# 02_PowerSupply.net
KiCad netlist of a schematic drawn in Altium Designer
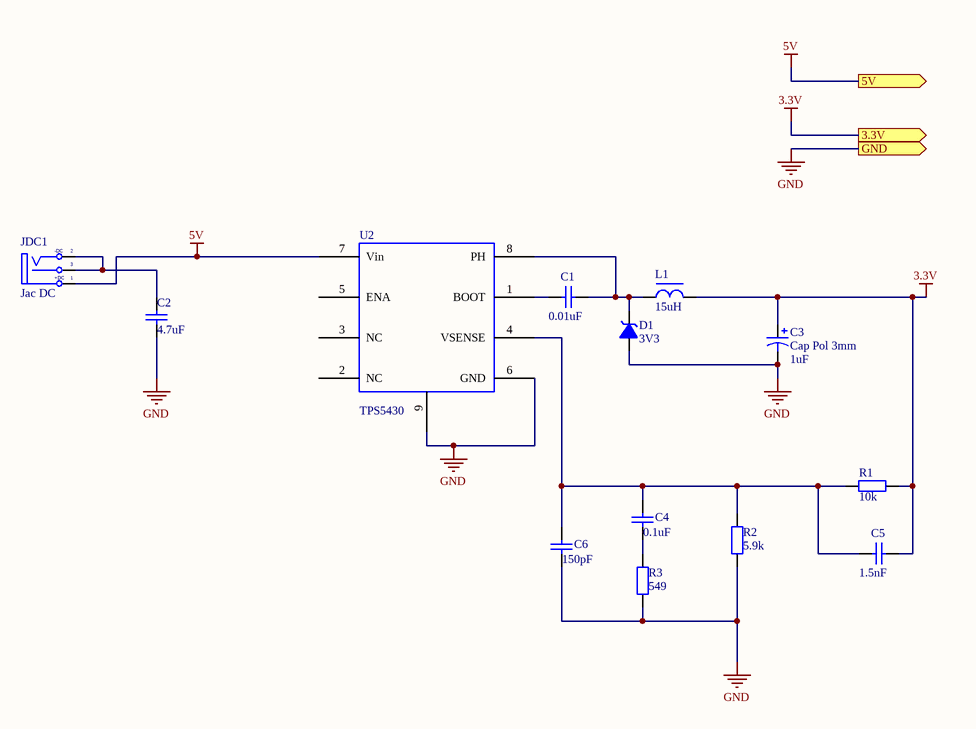
[diagram p0: 02_PowerSupply.SchDoc]

(export (version "E")
  (design (tool "Eeschema 10.0.6"))
  (components
    (comp (ref "C1")
      (value "0.01uF")
      (footprint "C0805")
      (description "Capacitor")
      (fields (field (name "PUBLISHER") "Altium Limited"))
      (libsource (lib "My Library") (part "CapSMD"))
    )
    (comp (ref "C2")
      (value "4.7uF")
      (footprint "C0805")
      (description "Capacitor")
      (fields (field (name "PUBLISHER") "Altium Limited"))
      (libsource (lib "My Library") (part "CapSMD"))
    )
    (comp (ref "C3")
      (value "Cap Pol 3mm")
      (footprint "C3MM")
      (description "Polarized Capacitor (Axial)")
      (fields (field (name "ALTIUM_UNNAMED_1") "1uF") (field (name "PUBLISHER") "Altium Limited"))
      (libsource (lib "My Library") (part "Cap Pol 3mm"))
    )
    (comp (ref "C4")
      (value "0.1uF")
      (footprint "C0805")
      (description "Capacitor")
      (fields (field (name "PUBLISHER") "Altium Limited"))
      (libsource (lib "My Library") (part "CapSMD"))
    )
    (comp (ref "C5")
      (value "1.5nF")
      (footprint "C0805")
      (description "Capacitor")
      (fields (field (name "PUBLISHER") "Altium Limited"))
      (libsource (lib "My Library") (part "CapSMD"))
    )
    (comp (ref "C6")
      (value "150pF")
      (footprint "C0805")
      (description "Capacitor")
      (fields (field (name "PUBLISHER") "Altium Limited"))
      (libsource (lib "My Library") (part "CapSMD"))
    )
    (comp (ref "D1")
      (value "3V3")
      (footprint "DZ0.5A")
      (description "Diode Zenner")
      (libsource (lib "My Library") (part "DZ"))
    )
    (comp (ref "JDC1")
      (value "Jac DC")
      (footprint "DC-IN")
      (description "Jac DC input")
      (libsource (lib "My Library") (part "DCIN"))
    )
    (comp (ref "L1")
      (value "15uH")
      (footprint "L-DIP-M-5.3")
      (description "Inductor")
      (libsource (lib "My Library") (part "L-DIP-1"))
    )
    (comp (ref "R1")
      (value "10k")
      (footprint "DIEN TRO 0805")
      (description "Resistor SMD 0805")
      (fields (field (name "Comment") "R0805") (field (name "PUBLISHER") "Altium Limited"))
      (libsource (lib "") (part "R0805_1"))
    )
    (comp (ref "R2")
      (value "5.9k")
      (footprint "DIEN TRO 0805")
      (description "Resistor SMD 0805")
      (fields (field (name "PUBLISHER") "Altium Limited"))
      (libsource (lib "My Library") (part "R0805"))
    )
    (comp (ref "R3")
      (value "549")
      (footprint "DIEN TRO 0805")
      (description "Resistor SMD 0805")
      (fields (field (name "Comment") "R0805") (field (name "PUBLISHER") "Altium Limited"))
      (libsource (lib "My Library") (part "R0805"))
    )
    (comp (ref "U2")
      (value "TPS5430")
      (footprint "TPS5430-2")
      (fields (field (name "NAME") "TPS5430"))
      (libsource (lib "My Library") (part "TPS5430"))
    )
  )
  (nets
    (net (code "1") (name "3.3V") (class "Default")
      (node (ref "C3") (pin "1") (pinfunction "1_1") (pintype "passive"))
      (node (ref "C5") (pin "1") (pinfunction "1_1") (pintype "passive"))
      (node (ref "L1") (pin "2") (pinfunction "2_2") (pintype "passive"))
      (node (ref "R1") (pin "2") (pinfunction "2_2") (pintype "passive"))
    )
    (net (code "2") (name "5V") (class "Default")
      (node (ref "JDC1") (pin "1") (pinfunction "T_1") (pintype "passive"))
      (node (ref "U2") (pin "7") (pinfunction "Vin_7") (pintype "passive"))
    )
    (net (code "3") (name "GND") (class "Default")
      (node (ref "C2") (pin "1") (pinfunction "1_1") (pintype "passive"))
      (node (ref "C3") (pin "2") (pinfunction "2_2") (pintype "passive"))
      (node (ref "C6") (pin "1") (pinfunction "1_1") (pintype "passive"))
      (node (ref "D1") (pin "1") (pinfunction "A_1") (pintype "passive"))
      (node (ref "R2") (pin "1") (pinfunction "1_1") (pintype "passive"))
      (node (ref "R3") (pin "1") (pinfunction "1_1") (pintype "passive"))
      (node (ref "U2") (pin "6") (pinfunction "GND_6") (pintype "passive"))
      (node (ref "U2") (pin "9") (pinfunction "PWR_PAD_9") (pintype "passive"))
    )
    (net (code "4") (name "Net-(C4-Pad1)") (class "Default")
      (node (ref "C4") (pin "1") (pinfunction "1_1") (pintype "passive"))
      (node (ref "R3") (pin "2") (pinfunction "2_2") (pintype "passive"))
    )
    (net (code "5") (name "Net-(D1-K)") (class "Default")
      (node (ref "C1") (pin "1") (pinfunction "1_1") (pintype "passive"))
      (node (ref "D1") (pin "2") (pinfunction "K_2") (pintype "passive"))
      (node (ref "L1") (pin "1") (pinfunction "1_1") (pintype "passive"))
      (node (ref "U2") (pin "8") (pinfunction "PH_8") (pintype "passive"))
    )
    (net (code "6") (name "Net-(JDC1-S)") (class "Default")
      (node (ref "C2") (pin "2") (pinfunction "2_2") (pintype "passive"))
      (node (ref "JDC1") (pin "2") (pinfunction "TN_2") (pintype "passive"))
      (node (ref "JDC1") (pin "3") (pinfunction "S_3") (pintype "power_in"))
    )
    (net (code "7") (name "Net-(U2-BOOT)") (class "Default")
      (node (ref "C1") (pin "2") (pinfunction "2_2") (pintype "passive"))
      (node (ref "U2") (pin "1") (pinfunction "BOOT_1") (pintype "passive"))
    )
    (net (code "8") (name "Net-(U2-VSENSE)") (class "Default")
      (node (ref "C4") (pin "2") (pinfunction "2_2") (pintype "passive"))
      (node (ref "C5") (pin "2") (pinfunction "2_2") (pintype "passive"))
      (node (ref "C6") (pin "2") (pinfunction "2_2") (pintype "passive"))
      (node (ref "R1") (pin "1") (pinfunction "1_1") (pintype "passive"))
      (node (ref "R2") (pin "2") (pinfunction "2_2") (pintype "passive"))
      (node (ref "U2") (pin "4") (pinfunction "VSENSE_4") (pintype "passive"))
    )
    (net (code "9") (name "unconnected-(U2-ENA-Pad5)") (class "Default")
      (node (ref "U2") (pin "5") (pinfunction "ENA_5") (pintype "passive"))
    )
    (net (code "10") (name "unconnected-(U2-NC-Pad2)") (class "Default")
      (node (ref "U2") (pin "2") (pinfunction "NC_2") (pintype "passive"))
    )
    (net (code "11") (name "unconnected-(U2-NC-Pad3)") (class "Default")
      (node (ref "U2") (pin "3") (pinfunction "NC_3") (pintype "passive"))
    )
  )
)
